# 4_-DISPLAY.net
KiCad netlist of a schematic drawn in Altium Designer
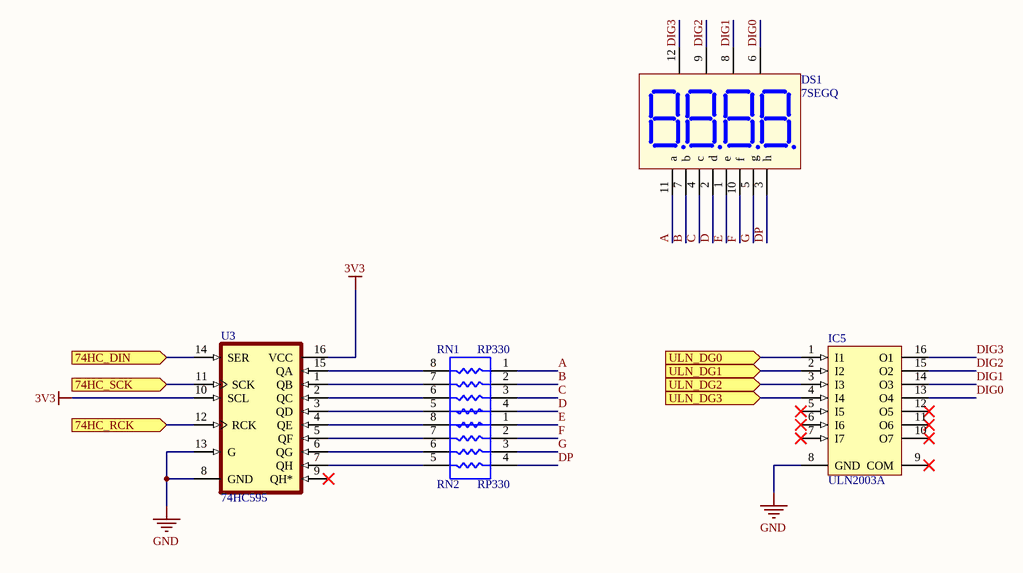
[diagram p0: [4]-DISPLAY.SchDoc]

(export (version "E")
  (design (tool "Eeschema 10.0.6"))
  (components
    (comp (ref "DS1")
      (value "7SEGQ")
      (footprint "LED7SEG-4-0.36")
      (description "Four 7 Seg Dipslay")
      (libsource (lib "My Library") (part "LED7SEG-4"))
    )
    (comp (ref "IC5")
      (value "ULN2003A")
      (footprint "SOIC16")
      (description "High-Voltage, High-Current Darlington Array")
      (fields (field (name "PUBLISHER") "Altium Limited"))
      (libsource (lib "My Library") (part "ULN2003A"))
    )
    (comp (ref "RN1") (value "RP330") (footprint "RN4-0805") (libsource (lib "My Library") (part "RN4-Dual")))
    (comp (ref "RN2") (value "RP330") (footprint "RN4-0805") (libsource (lib "My Library") (part "RN4-Dual")))
    (comp (ref "U3")
      (value "74HC595")
      (footprint "SOIC16")
      (description "8-bit Serial-Input/Serial or Parallel Output Shift Register with Latched 3-state Outputs")
      (libsource (lib "My Library") (part "74HC595"))
    )
  )
  (nets
    (net (code "1") (name "/74HC_DIN") (class "Default")
      (node (ref "U3") (pin "14") (pinfunction "SER_14") (pintype "input"))
    )
    (net (code "2") (name "/74HC_RCK") (class "Default")
      (node (ref "U3") (pin "12") (pinfunction "RCK_12") (pintype "input"))
    )
    (net (code "3") (name "/74HC_SCK") (class "Default")
      (node (ref "U3") (pin "11") (pinfunction "SCK_11") (pintype "input"))
    )
    (net (code "4") (name "/A") (class "Default")
      (node (ref "DS1") (pin "11") (pinfunction "a_11") (pintype "passive"))
      (node (ref "RN1") (pin "1") (pinfunction "1_1") (pintype "passive"))
    )
    (net (code "5") (name "/B") (class "Default")
      (node (ref "DS1") (pin "7") (pinfunction "b_7") (pintype "passive"))
      (node (ref "RN1") (pin "2") (pinfunction "2_2") (pintype "passive"))
    )
    (net (code "6") (name "/C") (class "Default")
      (node (ref "DS1") (pin "4") (pinfunction "c_4") (pintype "passive"))
      (node (ref "RN1") (pin "3") (pinfunction "3_3") (pintype "passive"))
    )
    (net (code "7") (name "/D") (class "Default")
      (node (ref "DS1") (pin "2") (pinfunction "d_2") (pintype "passive"))
      (node (ref "RN1") (pin "4") (pinfunction "4_4") (pintype "passive"))
    )
    (net (code "8") (name "/DIG0") (class "Default")
      (node (ref "DS1") (pin "6") (pinfunction "V4_6") (pintype "passive"))
      (node (ref "IC5") (pin "13") (pinfunction "O4_13") (pintype "open_collector"))
    )
    (net (code "9") (name "/DIG1") (class "Default")
      (node (ref "DS1") (pin "8") (pinfunction "V3_8") (pintype "passive"))
      (node (ref "IC5") (pin "14") (pinfunction "O3_14") (pintype "open_collector"))
    )
    (net (code "10") (name "/DIG2") (class "Default")
      (node (ref "DS1") (pin "9") (pinfunction "V2_9") (pintype "passive"))
      (node (ref "IC5") (pin "15") (pinfunction "O2_15") (pintype "open_collector"))
    )
    (net (code "11") (name "/DIG3") (class "Default")
      (node (ref "DS1") (pin "12") (pinfunction "V1_12") (pintype "passive"))
      (node (ref "IC5") (pin "16") (pinfunction "O1_16") (pintype "open_collector"))
    )
    (net (code "12") (name "/DP") (class "Default")
      (node (ref "DS1") (pin "3") (pinfunction "h_3") (pintype "passive"))
      (node (ref "RN2") (pin "4") (pinfunction "4_4") (pintype "passive"))
    )
    (net (code "13") (name "/E") (class "Default")
      (node (ref "DS1") (pin "1") (pinfunction "e_1") (pintype "passive"))
      (node (ref "RN2") (pin "1") (pinfunction "1_1") (pintype "passive"))
    )
    (net (code "14") (name "/F") (class "Default")
      (node (ref "DS1") (pin "10") (pinfunction "f_10") (pintype "passive"))
      (node (ref "RN2") (pin "2") (pinfunction "2_2") (pintype "passive"))
    )
    (net (code "15") (name "/G") (class "Default")
      (node (ref "DS1") (pin "5") (pinfunction "g_5") (pintype "passive"))
      (node (ref "RN2") (pin "3") (pinfunction "3_3") (pintype "passive"))
    )
    (net (code "16") (name "/ULN_DG0") (class "Default")
      (node (ref "IC5") (pin "1") (pinfunction "I1_1") (pintype "input"))
    )
    (net (code "17") (name "/ULN_DG1") (class "Default")
      (node (ref "IC5") (pin "2") (pinfunction "I2_2") (pintype "input"))
    )
    (net (code "18") (name "/ULN_DG2") (class "Default")
      (node (ref "IC5") (pin "3") (pinfunction "I3_3") (pintype "input"))
    )
    (net (code "19") (name "/ULN_DG3") (class "Default")
      (node (ref "IC5") (pin "4") (pinfunction "I4_4") (pintype "input"))
    )
    (net (code "20") (name "3V3") (class "Default")
      (node (ref "U3") (pin "10") (pinfunction "SCL_10") (pintype "input"))
      (node (ref "U3") (pin "16") (pinfunction "VCC_16") (pintype "power_in"))
    )
    (net (code "21") (name "GND") (class "Default")
      (node (ref "IC5") (pin "8") (pinfunction "GND_8") (pintype "power_in"))
      (node (ref "U3") (pin "13") (pinfunction "G_13") (pintype "input"))
      (node (ref "U3") (pin "8") (pinfunction "GND_8") (pintype "power_in"))
    )
    (net (code "22") (name "Net-(U3-QA)") (class "Default")
      (node (ref "RN1") (pin "8") (pinfunction "8_8") (pintype "passive"))
      (node (ref "U3") (pin "15") (pinfunction "QA_15") (pintype "input"))
    )
    (net (code "23") (name "Net-(U3-QB)") (class "Default")
      (node (ref "RN1") (pin "7") (pinfunction "7_7") (pintype "passive"))
      (node (ref "U3") (pin "1") (pinfunction "QB_1") (pintype "input"))
    )
    (net (code "24") (name "Net-(U3-QC)") (class "Default")
      (node (ref "RN1") (pin "6") (pinfunction "6_6") (pintype "passive"))
      (node (ref "U3") (pin "2") (pinfunction "QC_2") (pintype "input"))
    )
    (net (code "25") (name "Net-(U3-QD)") (class "Default")
      (node (ref "RN1") (pin "5") (pinfunction "5_5") (pintype "passive"))
      (node (ref "U3") (pin "3") (pinfunction "QD_3") (pintype "input"))
    )
    (net (code "26") (name "Net-(U3-QE)") (class "Default")
      (node (ref "RN2") (pin "8") (pinfunction "8_8") (pintype "passive"))
      (node (ref "U3") (pin "4") (pinfunction "QE_4") (pintype "input"))
    )
    (net (code "27") (name "Net-(U3-QF)") (class "Default")
      (node (ref "RN2") (pin "7") (pinfunction "7_7") (pintype "passive"))
      (node (ref "U3") (pin "5") (pinfunction "QF_5") (pintype "input"))
    )
    (net (code "28") (name "Net-(U3-QG)") (class "Default")
      (node (ref "RN2") (pin "6") (pinfunction "6_6") (pintype "passive"))
      (node (ref "U3") (pin "6") (pinfunction "QG_6") (pintype "input"))
    )
    (net (code "29") (name "Net-(U3-QH)") (class "Default")
      (node (ref "RN2") (pin "5") (pinfunction "5_5") (pintype "passive"))
      (node (ref "U3") (pin "7") (pinfunction "QH_7") (pintype "input"))
    )
    (net (code "30") (name "unconnected-(IC5-COM-Pad9)") (class "Default")
      (node (ref "IC5") (pin "9") (pinfunction "COM_9") (pintype "passive+no_connect"))
    )
    (net (code "31") (name "unconnected-(IC5-I5-Pad5)") (class "Default")
      (node (ref "IC5") (pin "5") (pinfunction "I5_5") (pintype "input+no_connect"))
    )
    (net (code "32") (name "unconnected-(IC5-I6-Pad6)") (class "Default")
      (node (ref "IC5") (pin "6") (pinfunction "I6_6") (pintype "input+no_connect"))
    )
    (net (code "33") (name "unconnected-(IC5-I7-Pad7)") (class "Default")
      (node (ref "IC5") (pin "7") (pinfunction "I7_7") (pintype "input+no_connect"))
    )
    (net (code "34") (name "unconnected-(IC5-O5-Pad12)") (class "Default")
      (node (ref "IC5") (pin "12") (pinfunction "O5_12") (pintype "open_collector+no_connect"))
    )
    (net (code "35") (name "unconnected-(IC5-O6-Pad11)") (class "Default")
      (node (ref "IC5") (pin "11") (pinfunction "O6_11") (pintype "open_collector+no_connect"))
    )
    (net (code "36") (name "unconnected-(IC5-O7-Pad10)") (class "Default")
      (node (ref "IC5") (pin "10") (pinfunction "O7_10") (pintype "open_collector+no_connect"))
    )
    (net (code "37") (name "unconnected-(U3-QH*-Pad9)") (class "Default")
      (node (ref "U3") (pin "9") (pinfunction "QH*_9") (pintype "input+no_connect"))
    )
  )
)
